# 555_devnight.net
KiCad netlist of a schematic drawn in EAGLE
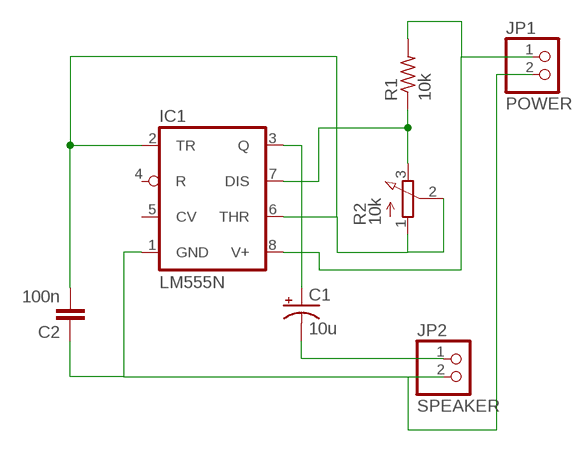
[diagram p0: schematic, sheet 1]

(export (version "E")
  (design (tool "Eeschema 10.0.6"))
  (components
    (comp (ref "C1")
      (value "10u")
      (footprint "eagle-import:E3,5-8")
      (libsource (lib "eagle-import") (part "CPOL-USE3.5-8"))
    )
    (comp (ref "C2")
      (value "100n")
      (footprint "eagle-import:C050-025X075")
      (libsource (lib "eagle-import") (part "C-EU050-025X075"))
    )
    (comp (ref "IC1")
      (value "LM555N")
      (footprint "eagle-import:DIL08-ROUND")
      (libsource (lib "eagle-import") (part "555NLM"))
    )
    (comp (ref "JP1")
      (value "POWER")
      (footprint "eagle-import:1X02")
      (libsource (lib "eagle-import") (part "PINHD-1X2"))
    )
    (comp (ref "JP2")
      (value "SPEAKER")
      (footprint "eagle-import:1X02")
      (libsource (lib "eagle-import") (part "PINHD-1X2"))
    )
    (comp (ref "R1")
      (value "10k")
      (footprint "eagle-import:0207_10")
      (libsource (lib "eagle-import") (part "R-US_0207/10"))
    )
    (comp (ref "R2")
      (value "10k")
      (footprint "eagle-import:3RP_1610N")
      (libsource (lib "eagle-import") (part "3RP/1610N"))
    )
  )
  (nets
    (net (code "1") (name "Net-(C1-Pad-)") (class "Default")
      (node (ref "C1") (pin "-") (pinfunction "-_-") (pintype "passive"))
      (node (ref "JP2") (pin "1") (pinfunction "1_1") (pintype "passive"))
    )
    (net (code "2") (name "Net-(IC1-DIS)") (class "Default")
      (node (ref "IC1") (pin "7") (pinfunction "DIS_7") (pintype "input"))
      (node (ref "R1") (pin "1") (pinfunction "1_1") (pintype "passive"))
      (node (ref "R2") (pin "3") (pinfunction "E_3") (pintype "passive"))
    )
    (net (code "3") (name "Net-(IC1-GND)") (class "Default")
      (node (ref "C2") (pin "1") (pinfunction "1_1") (pintype "passive"))
      (node (ref "IC1") (pin "1") (pinfunction "GND_1") (pintype "power_in"))
      (node (ref "JP1") (pin "2") (pinfunction "2_2") (pintype "passive"))
      (node (ref "JP2") (pin "2") (pinfunction "2_2") (pintype "passive"))
    )
    (net (code "4") (name "Net-(IC1-Q)") (class "Default")
      (node (ref "C1") (pin "+") (pinfunction "+_+") (pintype "passive"))
      (node (ref "IC1") (pin "3") (pinfunction "Q_3") (pintype "output"))
    )
    (net (code "5") (name "Net-(IC1-THR)") (class "Default")
      (node (ref "C2") (pin "2") (pinfunction "2_2") (pintype "passive"))
      (node (ref "IC1") (pin "2") (pinfunction "TR_2") (pintype "input"))
      (node (ref "IC1") (pin "6") (pinfunction "THR_6") (pintype "input"))
      (node (ref "R2") (pin "1") (pinfunction "A_1") (pintype "passive"))
      (node (ref "R2") (pin "2") (pinfunction "S_2") (pintype "passive"))
    )
    (net (code "6") (name "Net-(IC1-V+)") (class "Default")
      (node (ref "IC1") (pin "8") (pinfunction "V+_8") (pintype "power_in"))
      (node (ref "JP1") (pin "1") (pinfunction "1_1") (pintype "passive"))
      (node (ref "R1") (pin "2") (pinfunction "2_2") (pintype "passive"))
    )
    (net (code "7") (name "unconnected-(IC1-CV-Pad5)") (class "Default")
      (node (ref "IC1") (pin "5") (pinfunction "CV_5") (pintype "input"))
    )
    (net (code "8") (name "unconnected-(IC1-R-Pad4)") (class "Default")
      (node (ref "IC1") (pin "4") (pinfunction "R_4") (pintype "input"))
    )
  )
)
